# dc-dc_-12V-1A_0_2.net
KiCad netlist of a schematic drawn in EAGLE
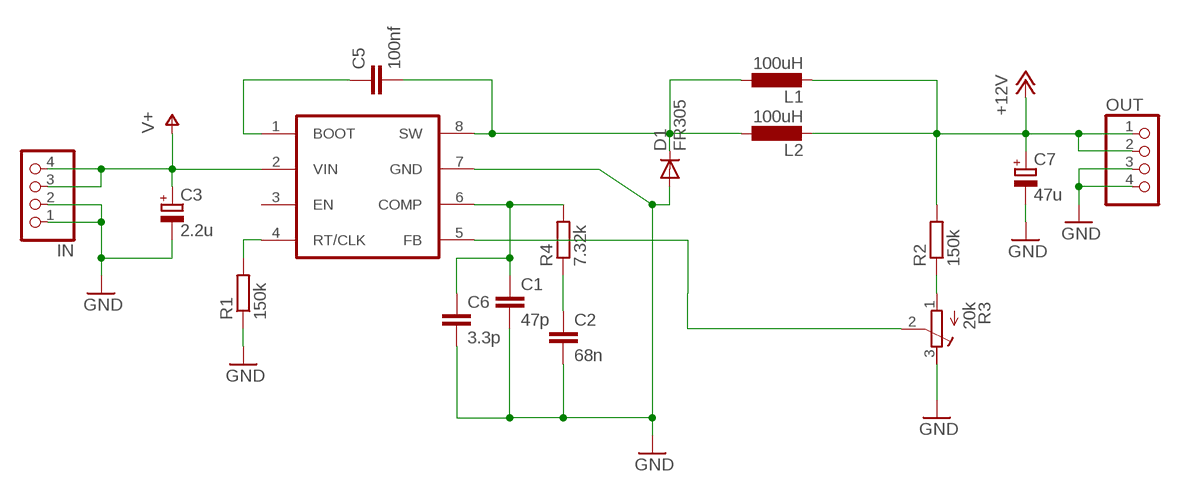
[diagram p0: schematic, sheet 1]

(export (version "E")
  (design (tool "Eeschema 10.0.6"))
  (components
    (comp (ref "C1")
      (value "47p")
      (footprint "eagle-import:C1206")
      (libsource (lib "eagle-import") (part "C-EUC1206"))
    )
    (comp (ref "C2")
      (value "68n")
      (footprint "eagle-import:C1206")
      (libsource (lib "eagle-import") (part "C-EUC1206"))
    )
    (comp (ref "C3")
      (value "2.2u")
      (footprint "eagle-import:E2-4")
      (libsource (lib "eagle-import") (part "CPOL-EUE2-4"))
    )
    (comp (ref "C5")
      (value "100nf")
      (footprint "eagle-import:C0805")
      (libsource (lib "eagle-import") (part "C-EUC0805"))
    )
    (comp (ref "C6")
      (value "3.3p")
      (footprint "eagle-import:C1206")
      (libsource (lib "eagle-import") (part "C-EUC1206"))
    )
    (comp (ref "C7")
      (value "47u")
      (footprint "eagle-import:E2-4")
      (libsource (lib "eagle-import") (part "CPOL-EUE2-4"))
    )
    (comp (ref "D1")
      (value "FR305")
      (footprint "eagle-import:DO201-15")
      (libsource (lib "eagle-import") (part "1N5400"))
    )
    (comp (ref "IN")
      (value "PINHD-1X4")
      (footprint "eagle-import:1X04")
      (libsource (lib "eagle-import") (part "PINHD-1X4"))
    )
    (comp (ref "L1")
      (value "100uH")
      (footprint "eagle-import:RCL_6000-XXXX-RC")
      (libsource (lib "eagle-import") (part "RCL_L-EU6000-XXX-RC"))
    )
    (comp (ref "L2")
      (value "100uH")
      (footprint "eagle-import:RCL_6000-XXXX-RC")
      (libsource (lib "eagle-import") (part "RCL_L-EU6000-XXX-RC"))
    )
    (comp (ref "OUT")
      (value "PINHD-1X4")
      (footprint "eagle-import:1X04")
      (libsource (lib "eagle-import") (part "PINHD-1X4"))
    )
    (comp (ref "R1")
      (value "150k")
      (footprint "eagle-import:R0805")
      (libsource (lib "eagle-import") (part "R-EU_R0805"))
    )
    (comp (ref "R2")
      (value "150k")
      (footprint "eagle-import:R0805")
      (libsource (lib "eagle-import") (part "R-EU_R0805"))
    )
    (comp (ref "R3")
      (value "20k")
      (footprint "eagle-import:RTRIM64X")
      (libsource (lib "eagle-import") (part "R-TRIMM64X"))
    )
    (comp (ref "R4")
      (value "7.32k")
      (footprint "eagle-import:0204_5")
      (libsource (lib "eagle-import") (part "R-EU_0204/5"))
    )
    (comp (ref "U1")
      (value "TPS54560")
      (footprint "eagle-import:SO08-POWERPAD")
      (libsource (lib "eagle-import") (part "TPS54560"))
    )
  )
  (nets
    (net (code "1") (name "+12V") (class "Default")
      (node (ref "C7") (pin "+") (pinfunction "+_+") (pintype "passive"))
      (node (ref "L1") (pin "2") (pinfunction "2_2") (pintype "passive"))
      (node (ref "L2") (pin "2") (pinfunction "2_2") (pintype "passive"))
      (node (ref "OUT") (pin "1") (pinfunction "1_1") (pintype "passive"))
      (node (ref "OUT") (pin "2") (pinfunction "2_2") (pintype "passive"))
      (node (ref "R2") (pin "2") (pinfunction "2_2") (pintype "passive"))
    )
    (net (code "2") (name "GND") (class "Default")
      (node (ref "C1") (pin "2") (pinfunction "2_2") (pintype "passive"))
      (node (ref "C2") (pin "2") (pinfunction "2_2") (pintype "passive"))
      (node (ref "C3") (pin "-") (pinfunction "-_-") (pintype "passive"))
      (node (ref "C6") (pin "2") (pinfunction "2_2") (pintype "passive"))
      (node (ref "C7") (pin "-") (pinfunction "-_-") (pintype "passive"))
      (node (ref "D1") (pin "A") (pinfunction "A_A") (pintype "passive"))
      (node (ref "IN") (pin "1") (pinfunction "1_1") (pintype "passive"))
      (node (ref "IN") (pin "2") (pinfunction "2_2") (pintype "passive"))
      (node (ref "OUT") (pin "3") (pinfunction "3_3") (pintype "passive"))
      (node (ref "OUT") (pin "4") (pinfunction "4_4") (pintype "passive"))
      (node (ref "R1") (pin "1") (pinfunction "1_1") (pintype "passive"))
      (node (ref "R3") (pin "3") (pinfunction "A_3") (pintype "passive"))
      (node (ref "U1") (pin "7") (pinfunction "GND_7") (pintype "input"))
    )
    (net (code "3") (name "Net-(C2-Pad1)") (class "Default")
      (node (ref "C2") (pin "1") (pinfunction "1_1") (pintype "passive"))
      (node (ref "R4") (pin "1") (pinfunction "1_1") (pintype "passive"))
    )
    (net (code "4") (name "Net-(R3-E)") (class "Default")
      (node (ref "R2") (pin "1") (pinfunction "1_1") (pintype "passive"))
      (node (ref "R3") (pin "1") (pinfunction "E_1") (pintype "passive"))
    )
    (net (code "5") (name "Net-(R3-S)") (class "Default")
      (node (ref "R3") (pin "2") (pinfunction "S_2") (pintype "passive"))
      (node (ref "U1") (pin "5") (pinfunction "FB_5") (pintype "passive"))
    )
    (net (code "6") (name "Net-(U1-BOOT)") (class "Default")
      (node (ref "C5") (pin "1") (pinfunction "1_1") (pintype "passive"))
      (node (ref "U1") (pin "1") (pinfunction "BOOT_1") (pintype "input"))
    )
    (net (code "7") (name "Net-(U1-COMP)") (class "Default")
      (node (ref "C1") (pin "1") (pinfunction "1_1") (pintype "passive"))
      (node (ref "C6") (pin "1") (pinfunction "1_1") (pintype "passive"))
      (node (ref "R4") (pin "2") (pinfunction "2_2") (pintype "passive"))
      (node (ref "U1") (pin "6") (pinfunction "COMP_6") (pintype "output"))
    )
    (net (code "8") (name "Net-(U1-RT{slash}CLK)") (class "Default")
      (node (ref "R1") (pin "2") (pinfunction "2_2") (pintype "passive"))
      (node (ref "U1") (pin "4") (pinfunction "RT/CLK_4") (pintype "input"))
    )
    (net (code "9") (name "Net-(U1-SW)") (class "Default")
      (node (ref "C5") (pin "2") (pinfunction "2_2") (pintype "passive"))
      (node (ref "D1") (pin "C") (pinfunction "C_C") (pintype "passive"))
      (node (ref "L1") (pin "1") (pinfunction "1_1") (pintype "passive"))
      (node (ref "L2") (pin "1") (pinfunction "1_1") (pintype "passive"))
      (node (ref "U1") (pin "8") (pinfunction "SW_8") (pintype "output"))
    )
    (net (code "10") (name "V+") (class "Default")
      (node (ref "C3") (pin "+") (pinfunction "+_+") (pintype "passive"))
      (node (ref "IN") (pin "3") (pinfunction "3_3") (pintype "passive"))
      (node (ref "IN") (pin "4") (pinfunction "4_4") (pintype "passive"))
      (node (ref "U1") (pin "2") (pinfunction "VIN_2") (pintype "input"))
    )
    (net (code "11") (name "unconnected-(U1-EN-Pad3)") (class "Default")
      (node (ref "U1") (pin "3") (pinfunction "EN_3") (pintype "input"))
    )
  )
)
